# tombol.net
KiCad netlist of a schematic drawn in EAGLE
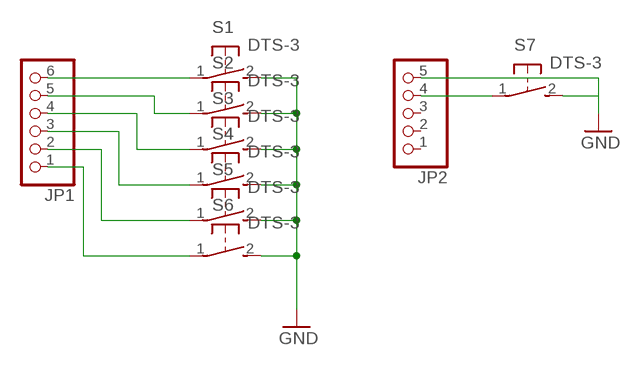
[diagram p0: schematic, sheet 1]

(export (version "E")
  (design (tool "Eeschema 10.0.6"))
  (components
    (comp (ref "JP1")
      (value "PINHD-1X6")
      (footprint "eagle-import:1X06")
      (libsource (lib "eagle-import") (part "PINHD-1X6"))
    )
    (comp (ref "JP2")
      (value "PINHD-1X5")
      (footprint "eagle-import:1X05")
      (libsource (lib "eagle-import") (part "PINHD-1X5"))
    )
    (comp (ref "S1")
      (value "DTS-3")
      (footprint "eagle-import:DTS-3")
      (libsource (lib "eagle-import") (part "DTS-3"))
    )
    (comp (ref "S2")
      (value "DTS-3")
      (footprint "eagle-import:DTS-3")
      (libsource (lib "eagle-import") (part "DTS-3"))
    )
    (comp (ref "S3")
      (value "DTS-3")
      (footprint "eagle-import:DTS-3")
      (libsource (lib "eagle-import") (part "DTS-3"))
    )
    (comp (ref "S4")
      (value "DTS-3")
      (footprint "eagle-import:DTS-3")
      (libsource (lib "eagle-import") (part "DTS-3"))
    )
    (comp (ref "S5")
      (value "DTS-3")
      (footprint "eagle-import:DTS-3")
      (libsource (lib "eagle-import") (part "DTS-3"))
    )
    (comp (ref "S6")
      (value "DTS-3")
      (footprint "eagle-import:DTS-3")
      (libsource (lib "eagle-import") (part "DTS-3"))
    )
    (comp (ref "S7")
      (value "DTS-3")
      (footprint "eagle-import:DTS-3")
      (libsource (lib "eagle-import") (part "DTS-3"))
    )
  )
  (nets
    (net (code "1") (name "GND") (class "Default")
      (node (ref "JP2") (pin "5") (pinfunction "5_5") (pintype "passive"))
      (node (ref "S1") (pin "2") (pinfunction "2_2") (pintype "passive"))
      (node (ref "S2") (pin "2") (pinfunction "2_2") (pintype "passive"))
      (node (ref "S3") (pin "2") (pinfunction "2_2") (pintype "passive"))
      (node (ref "S4") (pin "2") (pinfunction "2_2") (pintype "passive"))
      (node (ref "S5") (pin "2") (pinfunction "2_2") (pintype "passive"))
      (node (ref "S6") (pin "2") (pinfunction "2_2") (pintype "passive"))
      (node (ref "S7") (pin "2") (pinfunction "2_2") (pintype "passive"))
    )
    (net (code "2") (name "Net-(JP1-Pad1)") (class "Default")
      (node (ref "JP1") (pin "1") (pinfunction "1_1") (pintype "passive"))
      (node (ref "S6") (pin "1") (pinfunction "1_1") (pintype "passive"))
    )
    (net (code "3") (name "Net-(JP1-Pad2)") (class "Default")
      (node (ref "JP1") (pin "2") (pinfunction "2_2") (pintype "passive"))
      (node (ref "S5") (pin "1") (pinfunction "1_1") (pintype "passive"))
    )
    (net (code "4") (name "Net-(JP1-Pad3)") (class "Default")
      (node (ref "JP1") (pin "3") (pinfunction "3_3") (pintype "passive"))
      (node (ref "S4") (pin "1") (pinfunction "1_1") (pintype "passive"))
    )
    (net (code "5") (name "Net-(JP1-Pad4)") (class "Default")
      (node (ref "JP1") (pin "4") (pinfunction "4_4") (pintype "passive"))
      (node (ref "S3") (pin "1") (pinfunction "1_1") (pintype "passive"))
    )
    (net (code "6") (name "Net-(JP1-Pad5)") (class "Default")
      (node (ref "JP1") (pin "5") (pinfunction "5_5") (pintype "passive"))
      (node (ref "S2") (pin "1") (pinfunction "1_1") (pintype "passive"))
    )
    (net (code "7") (name "Net-(JP1-Pad6)") (class "Default")
      (node (ref "JP1") (pin "6") (pinfunction "6_6") (pintype "passive"))
      (node (ref "S1") (pin "1") (pinfunction "1_1") (pintype "passive"))
    )
    (net (code "8") (name "Net-(JP2-Pad4)") (class "Default")
      (node (ref "JP2") (pin "4") (pinfunction "4_4") (pintype "passive"))
      (node (ref "S7") (pin "1") (pinfunction "1_1") (pintype "passive"))
    )
    (net (code "9") (name "unconnected-(JP2-Pad1)") (class "Default")
      (node (ref "JP2") (pin "1") (pinfunction "1_1") (pintype "passive"))
    )
    (net (code "10") (name "unconnected-(JP2-Pad2)") (class "Default")
      (node (ref "JP2") (pin "2") (pinfunction "2_2") (pintype "passive"))
    )
    (net (code "11") (name "unconnected-(JP2-Pad3)") (class "Default")
      (node (ref "JP2") (pin "3") (pinfunction "3_3") (pintype "passive"))
    )
  )
)
